# mate_ROV_power2.net
KiCad netlist of a schematic drawn in EasyEDA Pro
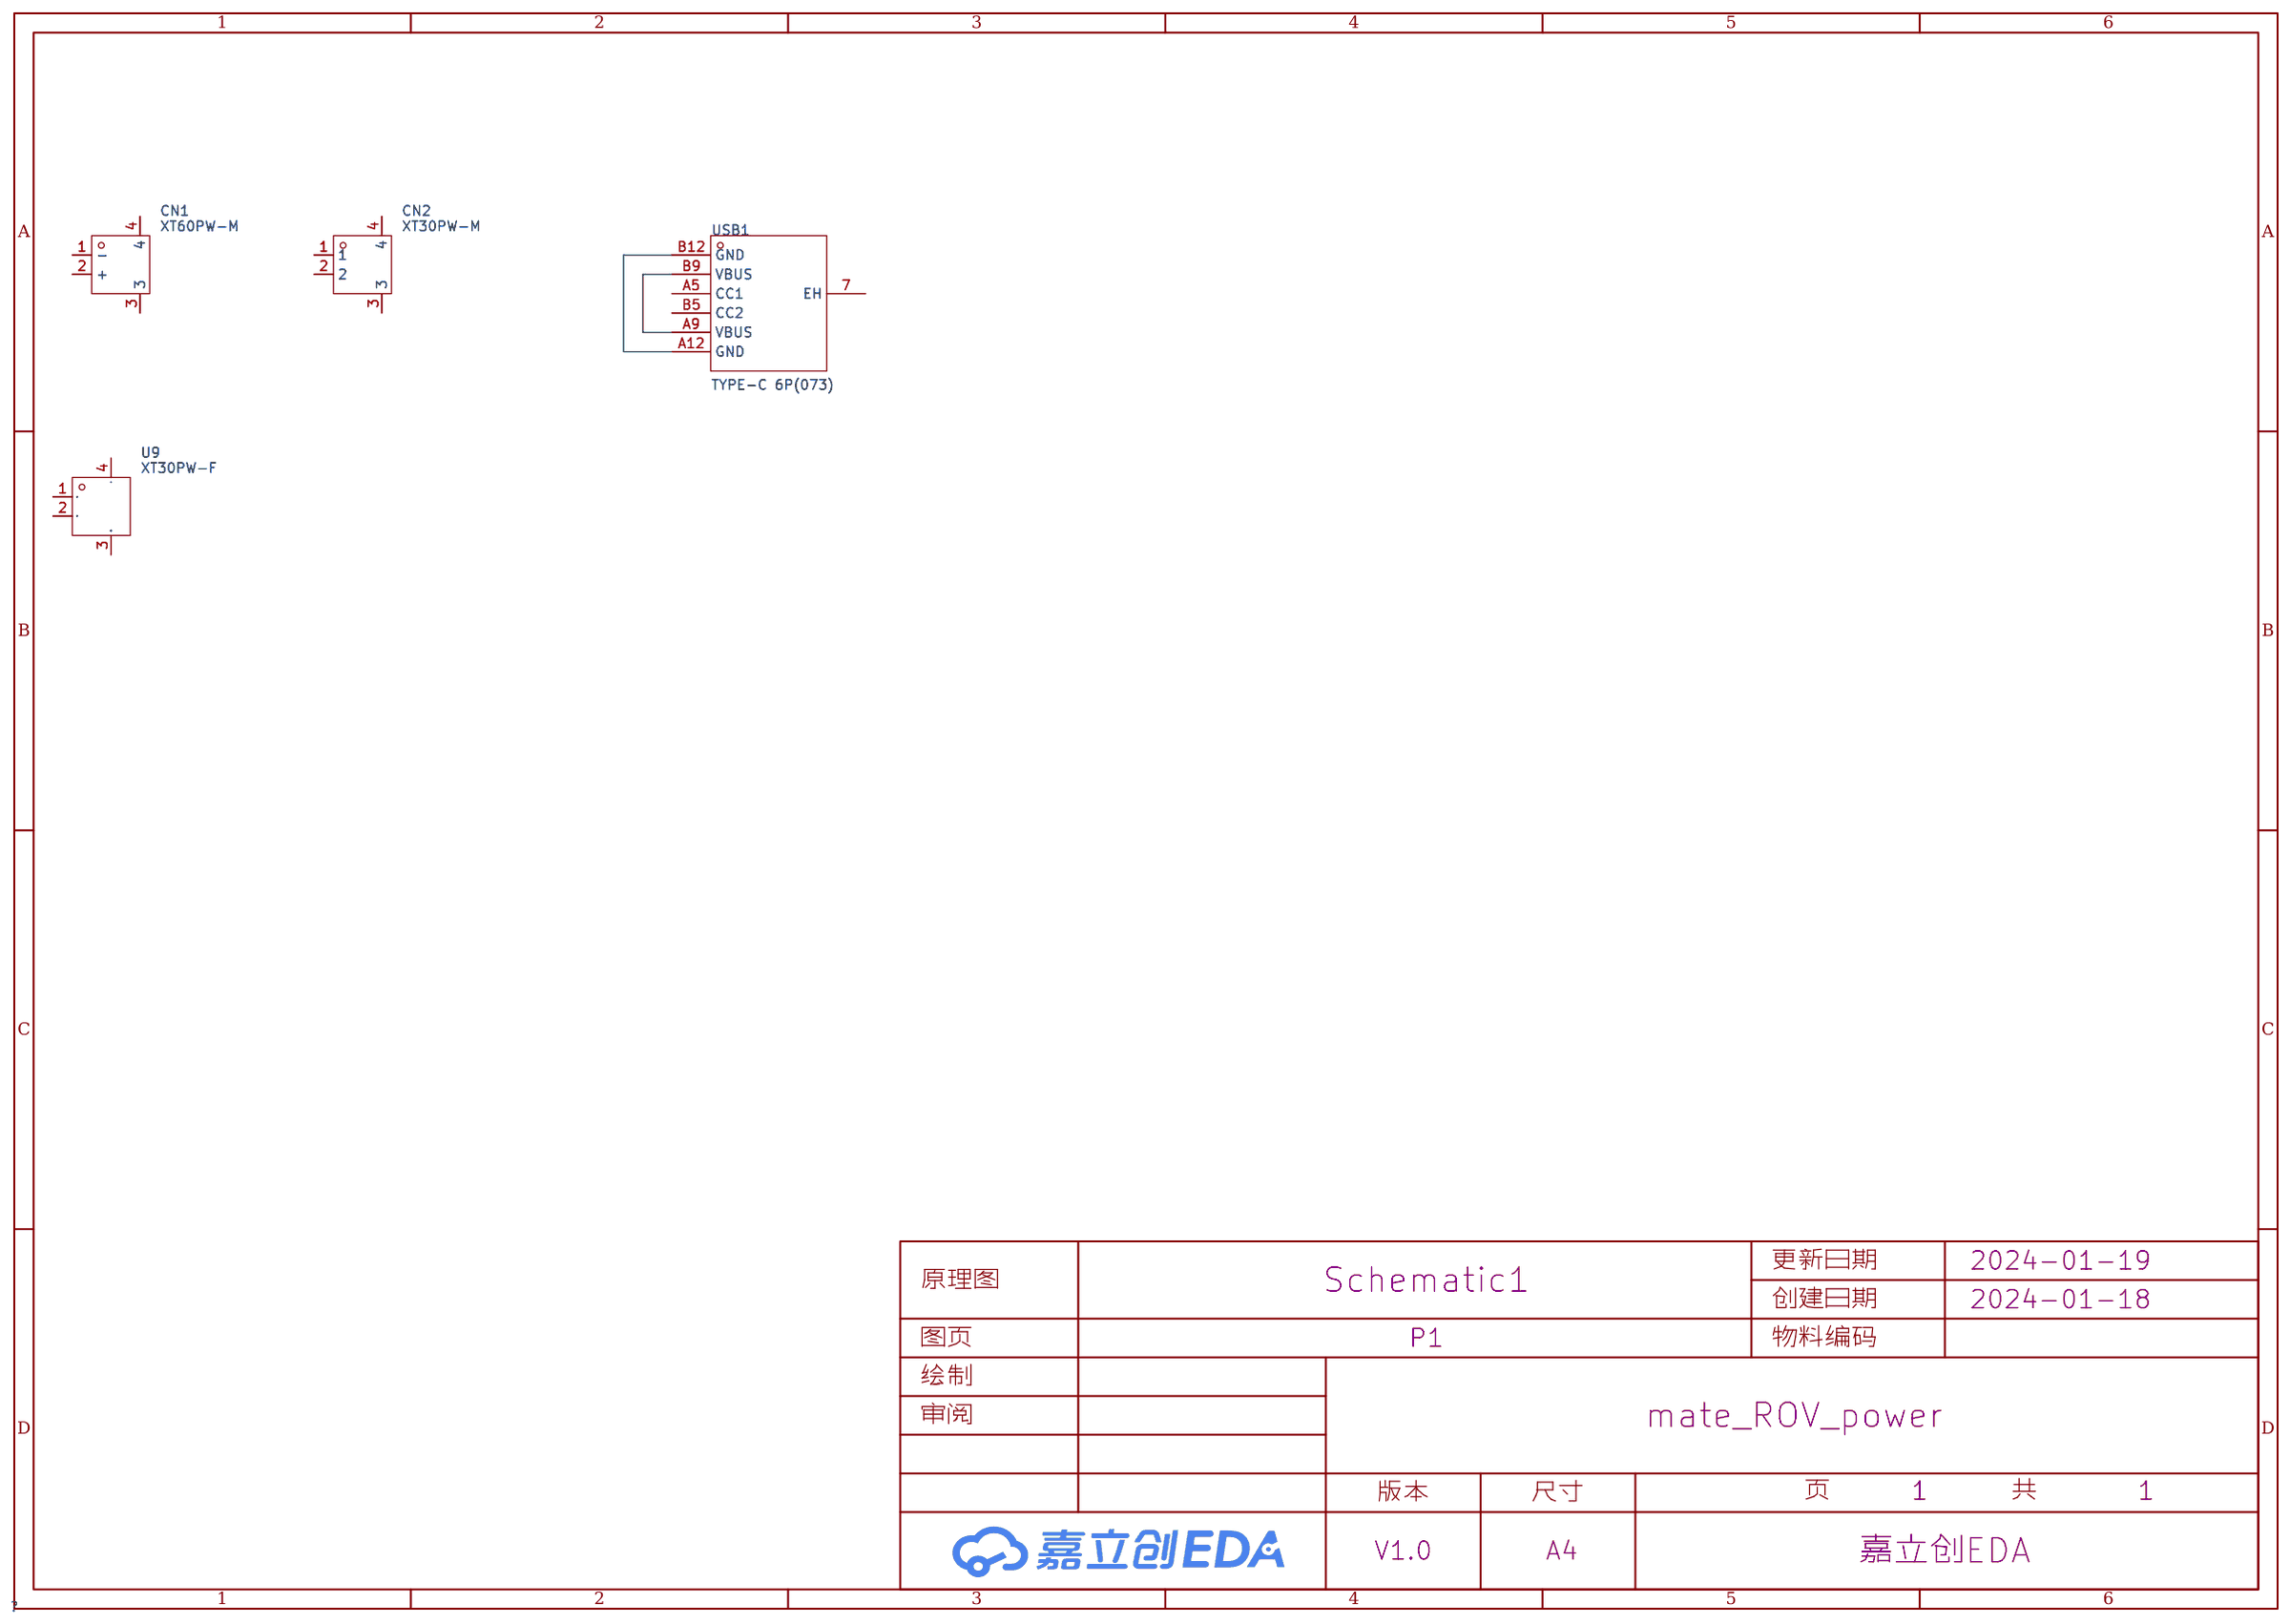
[diagram p0: schematic sheet]

(export (version "E")
  (design (tool "Eeschema 10.0.6"))
  (components
    (comp (ref "CN1")
      (value "XT60PW-M")
      (footprint "easyedapro:CONN-TH_XT60PW-M")
      (description "类别:-;类型1:-;")
      (fields (field (name "Manufacturer") "AMASS(艾迈斯)"))
      (libsource (lib "easyedapro") (part "XT60PW-M"))
    )
    (comp (ref "CN2")
      (value "XT30PW-M")
      (footprint "easyedapro:CONN-TH_XT30PW-M")
      (description "类别:-;类型1:-;")
      (fields (field (name "Manufacturer") "AMASS(艾迈斯)"))
      (libsource (lib "easyedapro") (part "XT30PW-M"))
    )
    (comp (ref "U9")
      (value "XT30PW-F")
      (footprint "easyedapro:CONN-TH_XT30PW-F-1")
      (description "类别:-;类型1:-;")
      (fields (field (name "Manufacturer") "AMASS(艾迈斯)"))
      (libsource (lib "easyedapro") (part "XT30PW-F"))
    )
    (comp (ref "USB1")
      (value "TYPE-C 6P(073)")
      (footprint "easyedapro:TYPE-C-SMD_TYPE-C-6P")
      (description "连接器类型:Type-C;标准:-;公母:母;端口数量:1;触点数量:6P;安装方式:卧贴;额定电流 - 电源:5A;工作温度范围:-25°C~+85°C;")
      (fields (field (name "Manufacturer") "SHOU HAN(首韩)"))
      (libsource (lib "easyedapro") (part "TYPE-C 6P(073)"))
    )
  )
  (nets
    (net (code "1") (name "Net-(USB1-GND-PadA12)") (class "Default")
      (node (ref "USB1") (pin "A12") (pinfunction "GND_A12") (pintype "unspecified"))
      (node (ref "USB1") (pin "B12") (pinfunction "GND_B12") (pintype "unspecified"))
    )
    (net (code "2") (name "Net-(USB1-VBUS-PadA9)") (class "Default")
      (node (ref "USB1") (pin "A9") (pinfunction "VBUS_A9") (pintype "unspecified"))
      (node (ref "USB1") (pin "B9") (pinfunction "VBUS_B9") (pintype "unspecified"))
    )
    (net (code "3") (name "unconnected-(CN1-+-Pad2)") (class "Default")
      (node (ref "CN1") (pin "2") (pinfunction "+_2") (pintype "unspecified"))
    )
    (net (code "4") (name "unconnected-(CN1---Pad1)") (class "Default")
      (node (ref "CN1") (pin "1") (pinfunction "-_1") (pintype "unspecified"))
    )
    (net (code "5") (name "unconnected-(CN1-Pad3)") (class "Default")
      (node (ref "CN1") (pin "3") (pinfunction "3_3") (pintype "unspecified"))
    )
    (net (code "6") (name "unconnected-(CN1-Pad4)") (class "Default")
      (node (ref "CN1") (pin "4") (pinfunction "4_4") (pintype "unspecified"))
    )
    (net (code "7") (name "unconnected-(CN2-Pad1)") (class "Default")
      (node (ref "CN2") (pin "1") (pinfunction "1_1") (pintype "unspecified"))
    )
    (net (code "8") (name "unconnected-(CN2-Pad2)") (class "Default")
      (node (ref "CN2") (pin "2") (pinfunction "2_2") (pintype "unspecified"))
    )
    (net (code "9") (name "unconnected-(CN2-Pad3)") (class "Default")
      (node (ref "CN2") (pin "3") (pinfunction "3_3") (pintype "unspecified"))
    )
    (net (code "10") (name "unconnected-(CN2-Pad4)") (class "Default")
      (node (ref "CN2") (pin "4") (pinfunction "4_4") (pintype "unspecified"))
    )
    (net (code "11") (name "unconnected-(U9-Pad1)") (class "Default")
      (node (ref "U9") (pin "1") (pinfunction "1_1") (pintype "unspecified"))
    )
    (net (code "12") (name "unconnected-(U9-Pad2)") (class "Default")
      (node (ref "U9") (pin "2") (pinfunction "2_2") (pintype "unspecified"))
    )
    (net (code "13") (name "unconnected-(U9-Pad3)") (class "Default")
      (node (ref "U9") (pin "3") (pinfunction "3_3") (pintype "unspecified"))
    )
    (net (code "14") (name "unconnected-(U9-Pad4)") (class "Default")
      (node (ref "U9") (pin "4") (pinfunction "4_4") (pintype "unspecified"))
    )
    (net (code "15") (name "unconnected-(USB1-CC1-PadA5)") (class "Default")
      (node (ref "USB1") (pin "A5") (pinfunction "CC1_A5") (pintype "unspecified"))
    )
    (net (code "16") (name "unconnected-(USB1-CC2-PadB5)") (class "Default")
      (node (ref "USB1") (pin "B5") (pinfunction "CC2_B5") (pintype "unspecified"))
    )
    (net (code "17") (name "unconnected-(USB1-EH-Pad7)") (class "Default")
      (node (ref "USB1") (pin "7") (pinfunction "EH_7") (pintype "unspecified"))
    )
  )
)
